# KoppRobotRevC.net
KiCad netlist of a schematic drawn in EAGLE
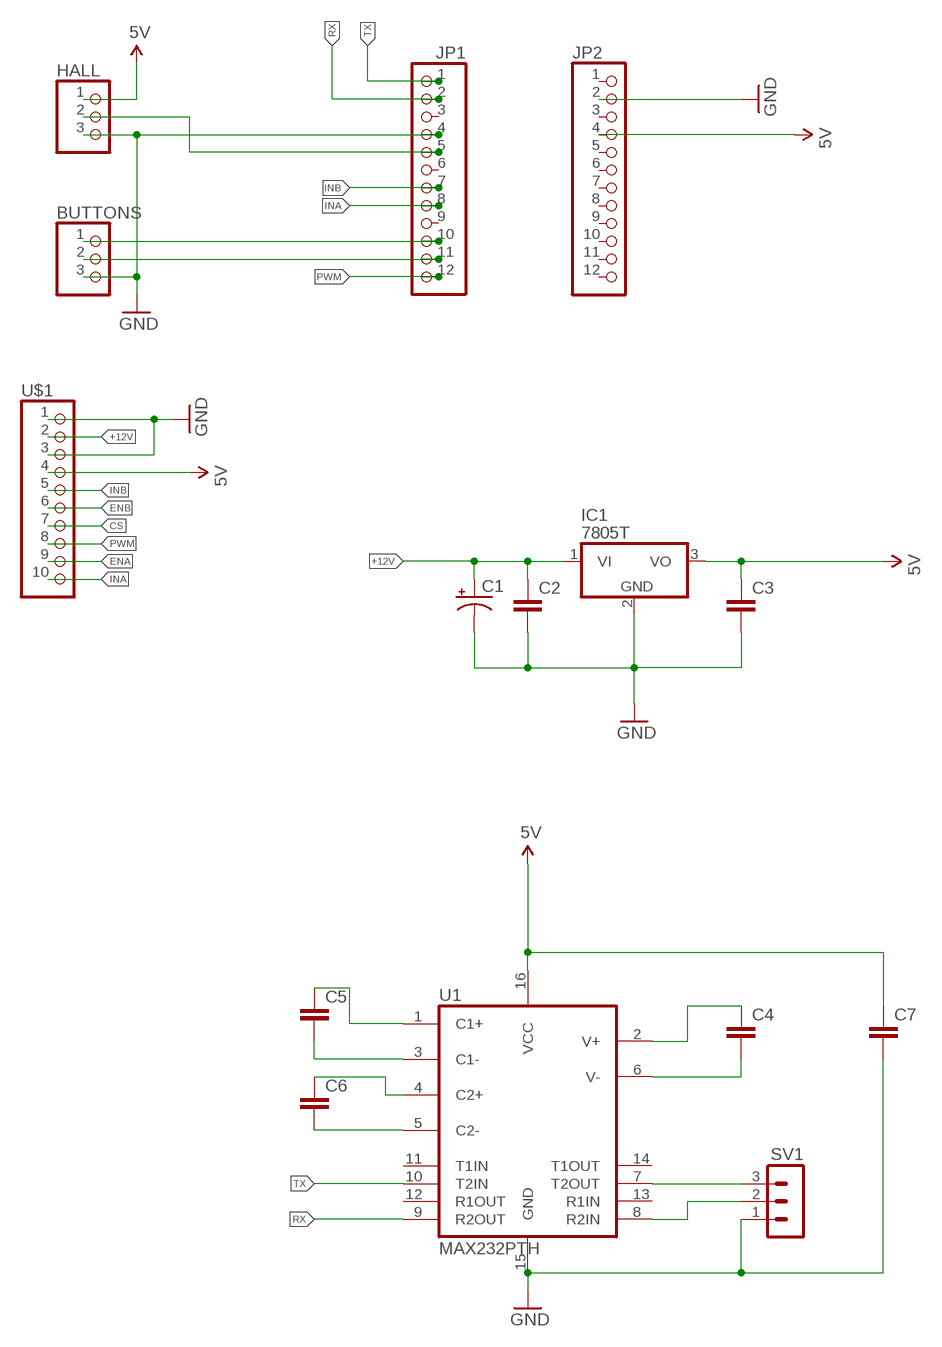
[diagram p0: schematic, sheet 1]

(export (version "E")
  (design (tool "Eeschema 10.0.6"))
  (components
    (comp (ref "BUTTONS")
      (value "PINHD-1X3")
      (footprint "eagle-import:1X03")
      (libsource (lib "eagle-import") (part "PINHD-1X3"))
    )
    (comp (ref "C1")
      (value "CAP_POLPTH3")
      (footprint "eagle-import:CPOL-RADIAL-1000UF-63V")
      (libsource (lib "eagle-import") (part "CAP_POLPTH3"))
    )
    (comp (ref "C2")
      (value "CAP0603-CAP")
      (footprint "eagle-import:0603-CAP")
      (libsource (lib "eagle-import") (part "CAP0603-CAP"))
    )
    (comp (ref "C3")
      (value "CAP0603-CAP")
      (footprint "eagle-import:0603-CAP")
      (libsource (lib "eagle-import") (part "CAP0603-CAP"))
    )
    (comp (ref "C4")
      (value "CAP0603-CAP")
      (footprint "eagle-import:0603-CAP")
      (libsource (lib "eagle-import") (part "CAP0603-CAP"))
    )
    (comp (ref "C5")
      (value "CAP0603-CAP")
      (footprint "eagle-import:0603-CAP")
      (libsource (lib "eagle-import") (part "CAP0603-CAP"))
    )
    (comp (ref "C6")
      (value "CAP0603-CAP")
      (footprint "eagle-import:0603-CAP")
      (libsource (lib "eagle-import") (part "CAP0603-CAP"))
    )
    (comp (ref "C7")
      (value "CAP0603-CAP")
      (footprint "eagle-import:0603-CAP")
      (libsource (lib "eagle-import") (part "CAP0603-CAP"))
    )
    (comp (ref "HALL")
      (value "PINHD-1X3")
      (footprint "eagle-import:1X03")
      (libsource (lib "eagle-import") (part "PINHD-1X3"))
    )
    (comp (ref "IC1")
      (value "7805T")
      (footprint "eagle-import:TO220H")
      (libsource (lib "eagle-import") (part "78T05"))
    )
    (comp (ref "JP1")
      (value "PINHD-1X12")
      (footprint "eagle-import:1X12")
      (libsource (lib "eagle-import") (part "PINHD-1X12"))
    )
    (comp (ref "JP2")
      (value "PINHD-1X12")
      (footprint "eagle-import:1X12")
      (libsource (lib "eagle-import") (part "PINHD-1X12"))
    )
    (comp (ref "SV1")
      (value "MA03-1")
      (footprint "eagle-import:MA03-1")
      (libsource (lib "eagle-import") (part "MA03-1"))
    )
    (comp (ref "U$1")
      (value "PINHD-1X10")
      (footprint "eagle-import:1X10")
      (libsource (lib "eagle-import") (part "PINHD-1X10"))
    )
    (comp (ref "U1")
      (value "MAX232PTH")
      (footprint "eagle-import:DIL16")
      (libsource (lib "eagle-import") (part "MAX232PTH"))
    )
  )
  (nets
    (net (code "1") (name "+12V") (class "Default")
      (node (ref "C1") (pin "1") (pinfunction "+_1") (pintype "passive"))
      (node (ref "C2") (pin "1") (pinfunction "1_1") (pintype "passive"))
      (node (ref "IC1") (pin "1") (pinfunction "VI_1") (pintype "input"))
      (node (ref "U$1") (pin "2") (pinfunction "2_2") (pintype "passive"))
    )
    (net (code "2") (name "5V") (class "Default")
      (node (ref "C3") (pin "1") (pinfunction "1_1") (pintype "passive"))
      (node (ref "C7") (pin "1") (pinfunction "1_1") (pintype "passive"))
      (node (ref "HALL") (pin "1") (pinfunction "1_1") (pintype "passive"))
      (node (ref "IC1") (pin "3") (pinfunction "VO_3") (pintype "passive"))
      (node (ref "JP2") (pin "4") (pinfunction "4_4") (pintype "passive"))
      (node (ref "U$1") (pin "4") (pinfunction "4_4") (pintype "passive"))
      (node (ref "U1") (pin "16") (pinfunction "VCC_16") (pintype "bidirectional"))
    )
    (net (code "3") (name "CS") (class "Default")
      (node (ref "U$1") (pin "7") (pinfunction "7_7") (pintype "passive"))
    )
    (net (code "4") (name "ENA") (class "Default")
      (node (ref "U$1") (pin "9") (pinfunction "9_9") (pintype "passive"))
    )
    (net (code "5") (name "ENB") (class "Default")
      (node (ref "U$1") (pin "6") (pinfunction "6_6") (pintype "passive"))
    )
    (net (code "6") (name "GND") (class "Default")
      (node (ref "BUTTONS") (pin "3") (pinfunction "3_3") (pintype "passive"))
      (node (ref "C1") (pin "2") (pinfunction "-_2") (pintype "passive"))
      (node (ref "C2") (pin "2") (pinfunction "2_2") (pintype "passive"))
      (node (ref "C3") (pin "2") (pinfunction "2_2") (pintype "passive"))
      (node (ref "C7") (pin "2") (pinfunction "2_2") (pintype "passive"))
      (node (ref "HALL") (pin "3") (pinfunction "3_3") (pintype "passive"))
      (node (ref "IC1") (pin "2") (pinfunction "GND_2") (pintype "passive"))
      (node (ref "JP1") (pin "4") (pinfunction "4_4") (pintype "passive"))
      (node (ref "JP2") (pin "2") (pinfunction "2_2") (pintype "passive"))
      (node (ref "SV1") (pin "1") (pinfunction "1_1") (pintype "passive"))
      (node (ref "U$1") (pin "1") (pinfunction "1_1") (pintype "passive"))
      (node (ref "U$1") (pin "3") (pinfunction "3_3") (pintype "passive"))
      (node (ref "U1") (pin "15") (pinfunction "GND_15") (pintype "bidirectional"))
    )
    (net (code "7") (name "INA") (class "Default")
      (node (ref "JP1") (pin "8") (pinfunction "8_8") (pintype "passive"))
      (node (ref "U$1") (pin "10") (pinfunction "10_10") (pintype "passive"))
    )
    (net (code "8") (name "INB") (class "Default")
      (node (ref "JP1") (pin "7") (pinfunction "7_7") (pintype "passive"))
      (node (ref "U$1") (pin "5") (pinfunction "5_5") (pintype "passive"))
    )
    (net (code "9") (name "Net-(BUTTONS-Pad1)") (class "Default")
      (node (ref "BUTTONS") (pin "1") (pinfunction "1_1") (pintype "passive"))
      (node (ref "JP1") (pin "10") (pinfunction "10_10") (pintype "passive"))
    )
    (net (code "10") (name "Net-(BUTTONS-Pad2)") (class "Default")
      (node (ref "BUTTONS") (pin "2") (pinfunction "2_2") (pintype "passive"))
      (node (ref "JP1") (pin "11") (pinfunction "11_11") (pintype "passive"))
    )
    (net (code "11") (name "Net-(HALL-Pad2)") (class "Default")
      (node (ref "HALL") (pin "2") (pinfunction "2_2") (pintype "passive"))
      (node (ref "JP1") (pin "5") (pinfunction "5_5") (pintype "passive"))
    )
    (net (code "12") (name "Net-(U1-C1+)") (class "Default")
      (node (ref "C5") (pin "1") (pinfunction "1_1") (pintype "passive"))
      (node (ref "U1") (pin "1") (pinfunction "C1+_1") (pintype "bidirectional"))
    )
    (net (code "13") (name "Net-(U1-C1-)") (class "Default")
      (node (ref "C5") (pin "2") (pinfunction "2_2") (pintype "passive"))
      (node (ref "U1") (pin "3") (pinfunction "C1-_3") (pintype "bidirectional"))
    )
    (net (code "14") (name "Net-(U1-C2+)") (class "Default")
      (node (ref "C6") (pin "1") (pinfunction "1_1") (pintype "passive"))
      (node (ref "U1") (pin "4") (pinfunction "C2+_4") (pintype "bidirectional"))
    )
    (net (code "15") (name "Net-(U1-C2-)") (class "Default")
      (node (ref "C6") (pin "2") (pinfunction "2_2") (pintype "passive"))
      (node (ref "U1") (pin "5") (pinfunction "C2-_5") (pintype "bidirectional"))
    )
    (net (code "16") (name "Net-(U1-R2IN)") (class "Default")
      (node (ref "SV1") (pin "2") (pinfunction "2_2") (pintype "passive"))
      (node (ref "U1") (pin "8") (pinfunction "R2IN_8") (pintype "input"))
    )
    (net (code "17") (name "Net-(U1-T2OUT)") (class "Default")
      (node (ref "SV1") (pin "3") (pinfunction "3_3") (pintype "passive"))
      (node (ref "U1") (pin "7") (pinfunction "T2OUT_7") (pintype "output"))
    )
    (net (code "18") (name "Net-(U1-V+)") (class "Default")
      (node (ref "C4") (pin "1") (pinfunction "1_1") (pintype "passive"))
      (node (ref "U1") (pin "2") (pinfunction "V+_2") (pintype "bidirectional"))
    )
    (net (code "19") (name "Net-(U1-V-)") (class "Default")
      (node (ref "C4") (pin "2") (pinfunction "2_2") (pintype "passive"))
      (node (ref "U1") (pin "6") (pinfunction "V-_6") (pintype "bidirectional"))
    )
    (net (code "20") (name "PWM") (class "Default")
      (node (ref "JP1") (pin "12") (pinfunction "12_12") (pintype "passive"))
      (node (ref "U$1") (pin "8") (pinfunction "8_8") (pintype "passive"))
    )
    (net (code "21") (name "RX") (class "Default")
      (node (ref "JP1") (pin "2") (pinfunction "2_2") (pintype "passive"))
      (node (ref "U1") (pin "9") (pinfunction "R2OUT_9") (pintype "output"))
    )
    (net (code "22") (name "TX") (class "Default")
      (node (ref "JP1") (pin "1") (pinfunction "1_1") (pintype "passive"))
      (node (ref "U1") (pin "10") (pinfunction "T2IN_10") (pintype "input"))
    )
    (net (code "23") (name "unconnected-(JP1-Pad3)") (class "Default")
      (node (ref "JP1") (pin "3") (pinfunction "3_3") (pintype "passive"))
    )
    (net (code "24") (name "unconnected-(JP1-Pad6)") (class "Default")
      (node (ref "JP1") (pin "6") (pinfunction "6_6") (pintype "passive"))
    )
    (net (code "25") (name "unconnected-(JP1-Pad9)") (class "Default")
      (node (ref "JP1") (pin "9") (pinfunction "9_9") (pintype "passive"))
    )
    (net (code "26") (name "unconnected-(JP2-Pad1)") (class "Default")
      (node (ref "JP2") (pin "1") (pinfunction "1_1") (pintype "passive"))
    )
    (net (code "27") (name "unconnected-(JP2-Pad3)") (class "Default")
      (node (ref "JP2") (pin "3") (pinfunction "3_3") (pintype "passive"))
    )
    (net (code "28") (name "unconnected-(JP2-Pad5)") (class "Default")
      (node (ref "JP2") (pin "5") (pinfunction "5_5") (pintype "passive"))
    )
    (net (code "29") (name "unconnected-(JP2-Pad6)") (class "Default")
      (node (ref "JP2") (pin "6") (pinfunction "6_6") (pintype "passive"))
    )
    (net (code "30") (name "unconnected-(JP2-Pad7)") (class "Default")
      (node (ref "JP2") (pin "7") (pinfunction "7_7") (pintype "passive"))
    )
    (net (code "31") (name "unconnected-(JP2-Pad8)") (class "Default")
      (node (ref "JP2") (pin "8") (pinfunction "8_8") (pintype "passive"))
    )
    (net (code "32") (name "unconnected-(JP2-Pad9)") (class "Default")
      (node (ref "JP2") (pin "9") (pinfunction "9_9") (pintype "passive"))
    )
    (net (code "33") (name "unconnected-(JP2-Pad10)") (class "Default")
      (node (ref "JP2") (pin "10") (pinfunction "10_10") (pintype "passive"))
    )
    (net (code "34") (name "unconnected-(JP2-Pad11)") (class "Default")
      (node (ref "JP2") (pin "11") (pinfunction "11_11") (pintype "passive"))
    )
    (net (code "35") (name "unconnected-(JP2-Pad12)") (class "Default")
      (node (ref "JP2") (pin "12") (pinfunction "12_12") (pintype "passive"))
    )
    (net (code "36") (name "unconnected-(U1-R1IN-Pad13)") (class "Default")
      (node (ref "U1") (pin "13") (pinfunction "R1IN_13") (pintype "input"))
    )
    (net (code "37") (name "unconnected-(U1-R1OUT-Pad12)") (class "Default")
      (node (ref "U1") (pin "12") (pinfunction "R1OUT_12") (pintype "output"))
    )
    (net (code "38") (name "unconnected-(U1-T1IN-Pad11)") (class "Default")
      (node (ref "U1") (pin "11") (pinfunction "T1IN_11") (pintype "input"))
    )
    (net (code "39") (name "unconnected-(U1-T1OUT-Pad14)") (class "Default")
      (node (ref "U1") (pin "14") (pinfunction "T1OUT_14") (pintype "output"))
    )
  )
)
